# schematic.net
KiCad netlist of a schematic drawn in EAGLE
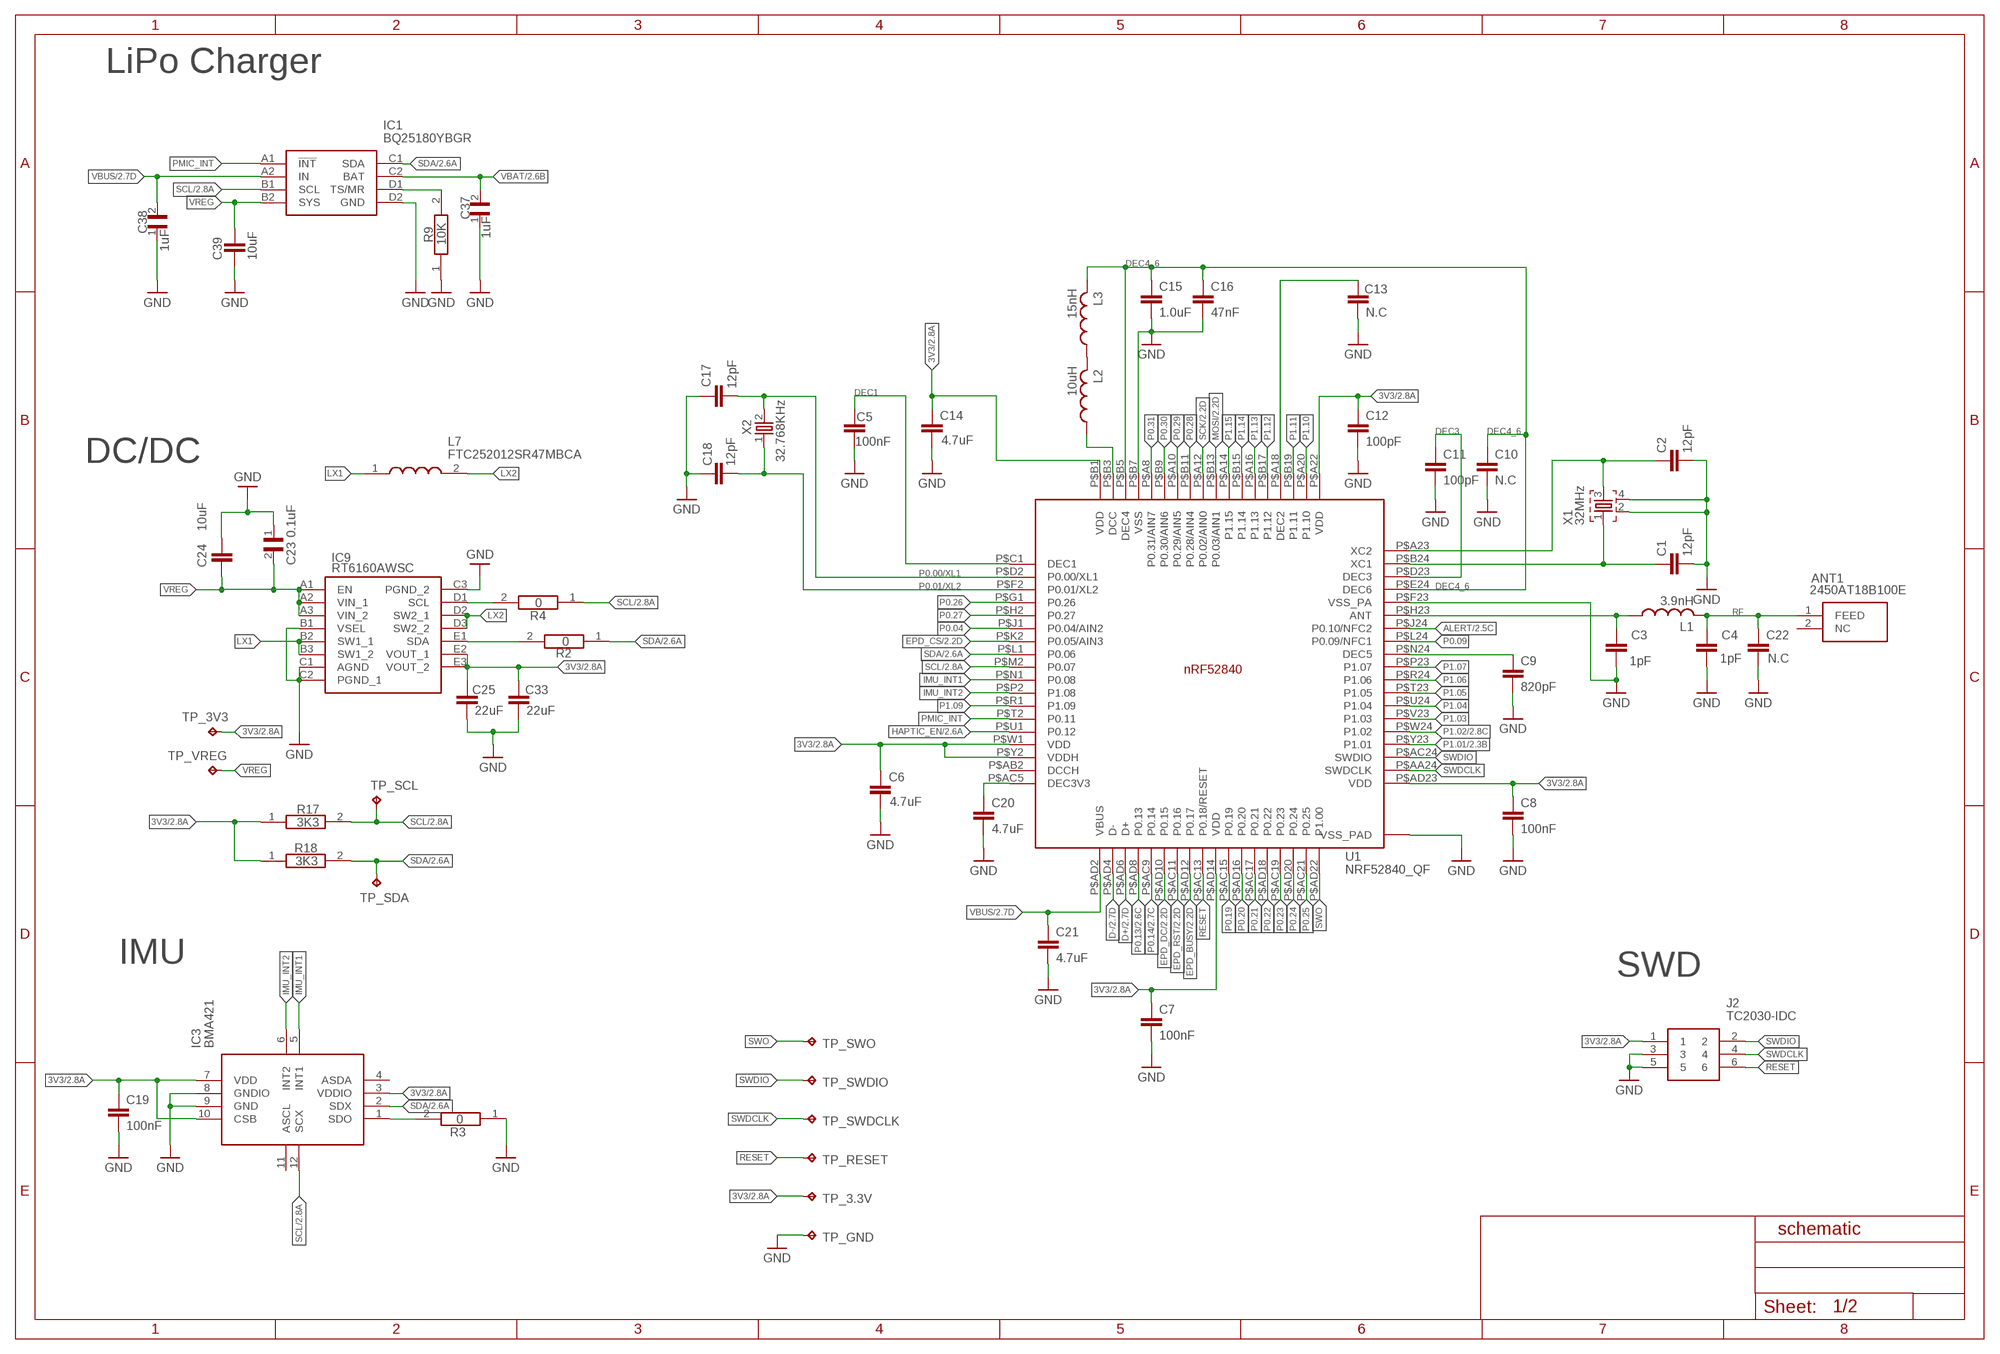
[diagram p0: schematic, sheet 1]
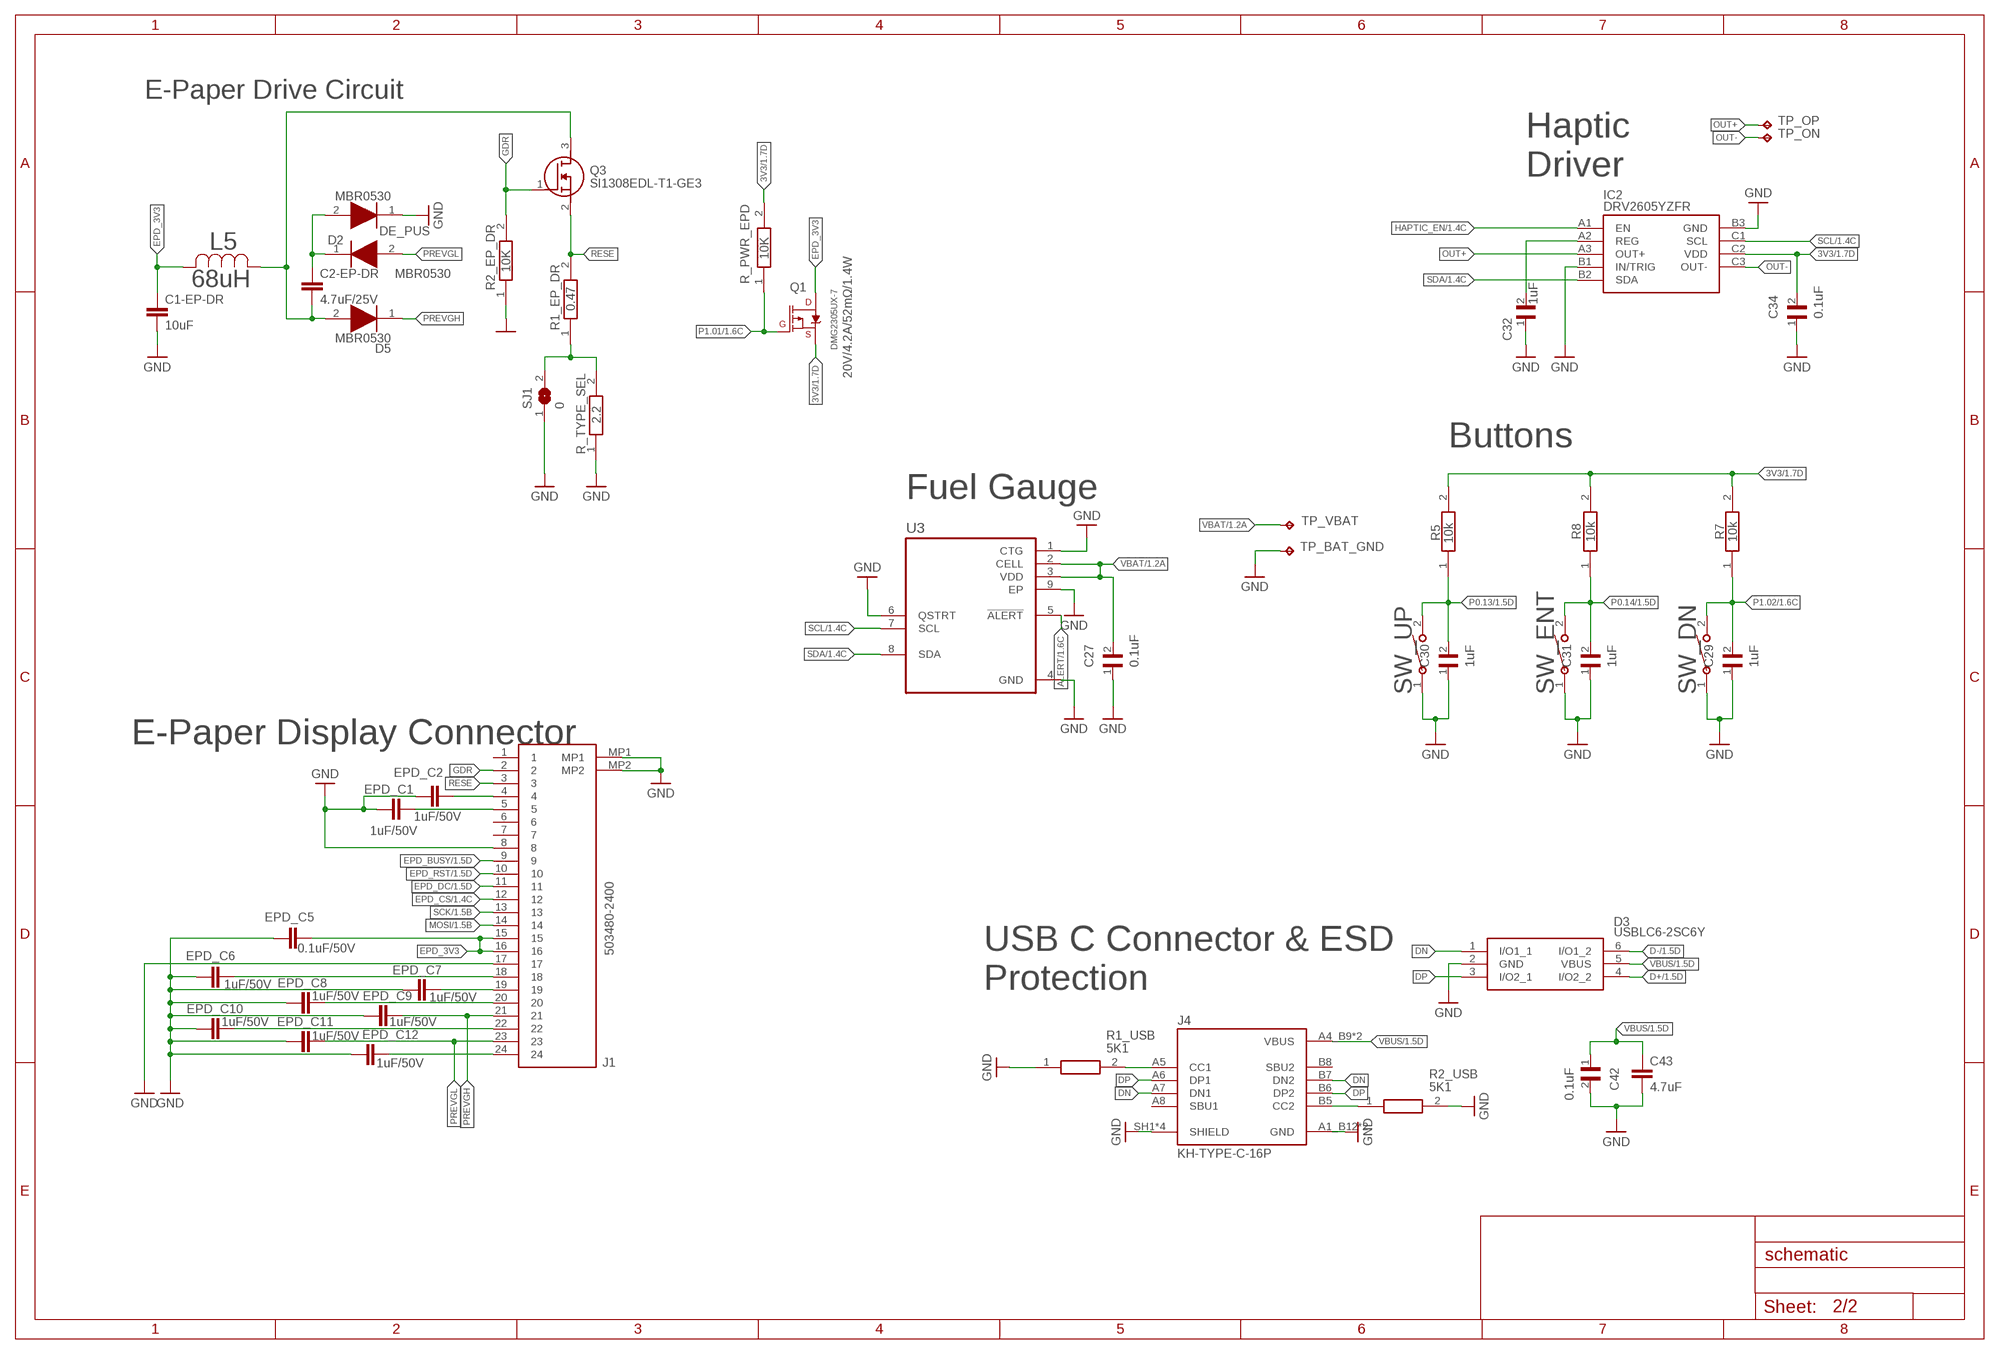
[diagram p1: schematic, sheet 2]

(export (version "E")
  (design (tool "Eeschema 10.0.6"))
  (components
    (comp (ref "ANT1")
      (value "2450AT18B100E")
      (footprint "eagle-import:2450AT18B100E_ANTC3216X140N")
      (fields (field (name "MOUSER_PART_NUMBER") "609-2450AT18B100E"))
      (libsource (lib "eagle-import") (part "2450AT18B100E_2450AT18B100E"))
    )
    (comp (ref "C1")
      (value "12pF")
      (footprint "eagle-import:NORDIC_NRF_3_RESC0201_L")
      (libsource (lib "eagle-import") (part "NORDIC_NRF_3_CAPACITOR_0201_L"))
    )
    (comp (ref "C2")
      (value "12pF")
      (footprint "eagle-import:NORDIC_NRF_3_RESC0201_L")
      (libsource (lib "eagle-import") (part "NORDIC_NRF_3_CAPACITOR_0201_L"))
    )
    (comp (ref "C3")
      (value "1pF")
      (footprint "eagle-import:NORDIC_NRF_3_RESC0201_L")
      (libsource (lib "eagle-import") (part "NORDIC_NRF_3_CAPACITOR_0201_L"))
    )
    (comp (ref "C4")
      (value "1pF")
      (footprint "eagle-import:NORDIC_NRF_3_RESC0201_L")
      (libsource (lib "eagle-import") (part "NORDIC_NRF_3_CAPACITOR_0201_L"))
    )
    (comp (ref "C5")
      (value "100nF")
      (footprint "eagle-import:NORDIC_NRF_3_RESC0201_L")
      (libsource (lib "eagle-import") (part "NORDIC_NRF_3_CAPACITOR_0201_L"))
    )
    (comp (ref "C6")
      (value "4.7uF")
      (footprint "eagle-import:NORDIC_NRF_3_RESC0402_L")
      (libsource (lib "eagle-import") (part "NORDIC_NRF_3_CAPACITOR_0402_L"))
    )
    (comp (ref "C7")
      (value "100nF")
      (footprint "eagle-import:NORDIC_NRF_3_RESC0201_L")
      (libsource (lib "eagle-import") (part "NORDIC_NRF_3_CAPACITOR_0201_L"))
    )
    (comp (ref "C8")
      (value "100nF")
      (footprint "eagle-import:NORDIC_NRF_3_RESC0201_L")
      (libsource (lib "eagle-import") (part "NORDIC_NRF_3_CAPACITOR_0201_L"))
    )
    (comp (ref "C9")
      (value "820pF")
      (footprint "eagle-import:NORDIC_NRF_3_RESC0201_L")
      (libsource (lib "eagle-import") (part "NORDIC_NRF_3_CAPACITOR_0201_L"))
    )
    (comp (ref "C10")
      (value "N.C")
      (footprint "eagle-import:NORDIC_NRF_3_RESC0201_L")
      (libsource (lib "eagle-import") (part "NORDIC_NRF_3_CAPACITOR_0201_L"))
    )
    (comp (ref "C11")
      (value "100pF")
      (footprint "eagle-import:NORDIC_NRF_3_RESC0201_L")
      (libsource (lib "eagle-import") (part "NORDIC_NRF_3_CAPACITOR_0201_L"))
    )
    (comp (ref "C12")
      (value "100pF")
      (footprint "eagle-import:NORDIC_NRF_3_RESC0201_L")
      (libsource (lib "eagle-import") (part "NORDIC_NRF_3_CAPACITOR_0201_L"))
    )
    (comp (ref "C13")
      (value "N.C")
      (footprint "eagle-import:NORDIC_NRF_3_RESC0201_L")
      (libsource (lib "eagle-import") (part "NORDIC_NRF_3_CAPACITOR_0201_L"))
    )
    (comp (ref "C14")
      (value "4.7uF")
      (footprint "eagle-import:NORDIC_NRF_3_RESC0402_L")
      (libsource (lib "eagle-import") (part "NORDIC_NRF_3_CAPACITOR_0402_L"))
    )
    (comp (ref "C15")
      (value "1.0uF")
      (footprint "eagle-import:NORDIC_NRF_3_RESC0402_L")
      (libsource (lib "eagle-import") (part "NORDIC_NRF_3_CAPACITOR_0402_L"))
    )
    (comp (ref "C16")
      (value "47nF")
      (footprint "eagle-import:NORDIC_NRF_3_RESC0201_L")
      (libsource (lib "eagle-import") (part "NORDIC_NRF_3_CAPACITOR_0201_L"))
    )
    (comp (ref "C17")
      (value "12pF")
      (footprint "eagle-import:NORDIC_NRF_3_RESC0201_L")
      (libsource (lib "eagle-import") (part "NORDIC_NRF_3_CAPACITOR_0201_L"))
    )
    (comp (ref "C18")
      (value "12pF")
      (footprint "eagle-import:NORDIC_NRF_3_RESC0201_L")
      (libsource (lib "eagle-import") (part "NORDIC_NRF_3_CAPACITOR_0201_L"))
    )
    (comp (ref "C19")
      (value "100nF")
      (footprint "eagle-import:NORDIC_NRF_3_RESC0201_L")
      (libsource (lib "eagle-import") (part "NORDIC_NRF_3_CAPACITOR_0201_L"))
    )
    (comp (ref "C20")
      (value "4.7uF")
      (footprint "eagle-import:NORDIC_NRF_3_RESC0402_L")
      (libsource (lib "eagle-import") (part "NORDIC_NRF_3_CAPACITOR_0402_L"))
    )
    (comp (ref "C21")
      (value "4.7uF")
      (footprint "eagle-import:NORDIC_NRF_3_RESC0402_L")
      (libsource (lib "eagle-import") (part "NORDIC_NRF_3_CAPACITOR_0402_L"))
    )
    (comp (ref "C22")
      (value "N.C")
      (footprint "eagle-import:NORDIC_NRF_3_RESC0201_L")
      (libsource (lib "eagle-import") (part "NORDIC_NRF_3_CAPACITOR_0201_L"))
    )
    (comp (ref "C23")
      (value "0.1uF")
      (footprint "eagle-import:GRM011R60J152KE01L_2_CAPC0201X13N")
      (fields (field (name "MF") "Murata") (field (name "MP") "GRM011R60J152KE01L"))
      (libsource (lib "eagle-import") (part "GRM011R60J152KE01L_2_GRM011R60J152KE01L"))
    )
    (comp (ref "C24")
      (value "10uF")
      (footprint "eagle-import:NORDIC_NRF_3_RESC0402_L")
      (libsource (lib "eagle-import") (part "NORDIC_NRF_3_CAPACITOR_0402_L"))
    )
    (comp (ref "C25")
      (value "22uF")
      (footprint "eagle-import:NORDIC_NRF_3_RESC0402_L")
      (libsource (lib "eagle-import") (part "NORDIC_NRF_3_CAPACITOR_0402_L"))
    )
    (comp (ref "C33")
      (value "22uF")
      (footprint "eagle-import:NORDIC_NRF_3_RESC0402_L")
      (libsource (lib "eagle-import") (part "NORDIC_NRF_3_CAPACITOR_0402_L"))
    )
    (comp (ref "C37")
      (value "1uF")
      (footprint "eagle-import:GRM011R60J152KE01L_2_CAPC0201X13N")
      (fields (field (name "MF") "Murata") (field (name "MP") "GRM011R60J152KE01L"))
      (libsource (lib "eagle-import") (part "GRM011R60J152KE01L_2_GRM011R60J152KE01L"))
    )
    (comp (ref "C38")
      (value "1uF")
      (footprint "eagle-import:GRM011R60J152KE01L_2_CAPC0201X13N")
      (fields (field (name "MF") "Murata") (field (name "MP") "GRM011R60J152KE01L"))
      (libsource (lib "eagle-import") (part "GRM011R60J152KE01L_2_GRM011R60J152KE01L"))
    )
    (comp (ref "C39")
      (value "10uF")
      (footprint "eagle-import:NORDIC_NRF_3_RESC0402_L")
      (libsource (lib "eagle-import") (part "NORDIC_NRF_3_CAPACITOR_0402_L"))
    )
    (comp (ref "IC1")
      (value "BQ25180YBGR")
      (footprint "eagle-import:BQ25180YBGR_BGA8C40P2X4_100X155X50")
      (fields (field (name "MOUSER_PART_NUMBER") "595-BQ25180YBGR"))
      (libsource (lib "eagle-import") (part "BQ25180YBGR_BQ25180YBGR"))
    )
    (comp (ref "IC3")
      (value "BMA421")
      (footprint "eagle-import:BMA423_BMA423")
      (fields (field (name "ARROW_PART_NUMBER") "BMA423") (field (name "MOUSER_PART_NUMBER") "262-BMA423"))
      (libsource (lib "eagle-import") (part "BMA423_BMA423"))
    )
    (comp (ref "IC9")
      (value "RT6160AWSC")
      (footprint "eagle-import:RT6160AWSC_BGA15C40P3X5_140X230X60")
      (fields (field (name "MOUSER_PART_NUMBER") "835-RT6160AWSC"))
      (libsource (lib "eagle-import") (part "RT6160AWSC_RT6160AWSC"))
    )
    (comp (ref "J2")
      (value "TC2030-IDC")
      (footprint "eagle-import:TC2030-IDC_TC2030IDC")
      (libsource (lib "eagle-import") (part "TC2030-IDC_TC2030-IDC"))
    )
    (comp (ref "L1")
      (value "3.9nH")
      (footprint "eagle-import:NORDIC_NRF_2_RESC0402_L")
      (libsource (lib "eagle-import") (part "NORDIC_NRF_2_INDUCTOR_0402_L"))
    )
    (comp (ref "L2")
      (value "10uH")
      (footprint "eagle-import:NORDIC_NRF_2_RESC0603_L")
      (libsource (lib "eagle-import") (part "NORDIC_NRF_2_INDUCTOR_0603_L"))
    )
    (comp (ref "L3")
      (value "15nH")
      (footprint "eagle-import:NORDIC_NRF_2_RESC0201_L")
      (libsource (lib "eagle-import") (part "NORDIC_NRF_2_INDUCTOR_0201_L"))
    )
    (comp (ref "L7")
      (value "FTC252012SR47MBCA")
      (footprint "eagle-import:MLP2016SR47MT0S1_INDC2016X100N")
      (libsource (lib "eagle-import") (part "MLP2016SR47MT0S1_FTC252012SR47MBCA"))
    )
    (comp (ref "R2")
      (value "0")
      (footprint "eagle-import:CPF0201D7K68C1_0201")
      (libsource (lib "eagle-import") (part "CPF0201D7K68C1_CPF0201D7K68C1"))
    )
    (comp (ref "R3")
      (value "0")
      (footprint "eagle-import:CPF0201D7K68C1_0201")
      (libsource (lib "eagle-import") (part "CPF0201D7K68C1_CPF0201D7K68C1"))
    )
    (comp (ref "R4")
      (value "0")
      (footprint "eagle-import:CPF0201D7K68C1_0201")
      (libsource (lib "eagle-import") (part "CPF0201D7K68C1_CPF0201D7K68C1"))
    )
    (comp (ref "R9")
      (value "10K")
      (footprint "eagle-import:CPF0201D7K68C1_0201")
      (libsource (lib "eagle-import") (part "CPF0201D7K68C1_CPF0201D7K68C1"))
    )
    (comp (ref "R17")
      (value "3K3")
      (footprint "eagle-import:CPF0201D7K68C1_0201")
      (libsource (lib "eagle-import") (part "CPF0201D7K68C1_CPF0201D7K68C1"))
    )
    (comp (ref "R18")
      (value "3K3")
      (footprint "eagle-import:CPF0201D7K68C1_0201")
      (libsource (lib "eagle-import") (part "CPF0201D7K68C1_CPF0201D7K68C1"))
    )
    (comp (ref "TP_3.3V")
      (value "HECTOR_WATCH_1_TPTP20R")
      (footprint "eagle-import:HECTOR_WATCH_1_TP20R")
      (libsource (lib "eagle-import") (part "HECTOR_WATCH_1_TPTP20R"))
    )
    (comp (ref "TP_3V3")
      (value "HECTOR_WATCH_1_TPTP20R")
      (footprint "eagle-import:HECTOR_WATCH_1_TP20R")
      (libsource (lib "eagle-import") (part "HECTOR_WATCH_1_TPTP20R"))
    )
    (comp (ref "TP_GND")
      (value "HECTOR_WATCH_1_TPTP20R")
      (footprint "eagle-import:HECTOR_WATCH_1_TP20R")
      (libsource (lib "eagle-import") (part "HECTOR_WATCH_1_TPTP20R"))
    )
    (comp (ref "TP_RESET")
      (value "HECTOR_WATCH_1_TPTP20R")
      (footprint "eagle-import:HECTOR_WATCH_1_TP20R")
      (libsource (lib "eagle-import") (part "HECTOR_WATCH_1_TPTP20R"))
    )
    (comp (ref "TP_SCL")
      (value "HECTOR_WATCH_1_TPTP20R")
      (footprint "eagle-import:HECTOR_WATCH_1_TP20R")
      (libsource (lib "eagle-import") (part "HECTOR_WATCH_1_TPTP20R"))
    )
    (comp (ref "TP_SDA")
      (value "HECTOR_WATCH_1_TPTP20R")
      (footprint "eagle-import:HECTOR_WATCH_1_TP20R")
      (libsource (lib "eagle-import") (part "HECTOR_WATCH_1_TPTP20R"))
    )
    (comp (ref "TP_SWDCLK")
      (value "HECTOR_WATCH_1_TPTP20R")
      (footprint "eagle-import:HECTOR_WATCH_1_TP20R")
      (libsource (lib "eagle-import") (part "HECTOR_WATCH_1_TPTP20R"))
    )
    (comp (ref "TP_SWDIO")
      (value "HECTOR_WATCH_1_TPTP20R")
      (footprint "eagle-import:HECTOR_WATCH_1_TP20R")
      (libsource (lib "eagle-import") (part "HECTOR_WATCH_1_TPTP20R"))
    )
    (comp (ref "TP_SWO")
      (value "HECTOR_WATCH_1_TPTP20R")
      (footprint "eagle-import:HECTOR_WATCH_1_TP20R")
      (libsource (lib "eagle-import") (part "HECTOR_WATCH_1_TPTP20R"))
    )
    (comp (ref "TP_VREG")
      (value "HECTOR_WATCH_1_TPTP20R")
      (footprint "eagle-import:HECTOR_WATCH_1_TP20R")
      (libsource (lib "eagle-import") (part "HECTOR_WATCH_1_TPTP20R"))
    )
    (comp (ref "U1")
      (value "NRF52840_QF")
      (footprint "eagle-import:NORDIC_NRF_4_AQFN50P700X700X85_HS-74N")
      (libsource (lib "eagle-import") (part "NORDIC_NRF_4_NRF52840_QF"))
    )
    (comp (ref "X1")
      (value "32MHz")
      (footprint "eagle-import:NORDIC_NRF_BT-XTAL_2016_N")
      (libsource (lib "eagle-import") (part "NORDIC_NRF_XTAL_32MHZ"))
    )
    (comp (ref "X2")
      (value "32.768KHz")
      (footprint "eagle-import:NORDIC_NRF_1_XTAL_3215_N")
      (libsource (lib "eagle-import") (part "NORDIC_NRF_1_XTAL_32KHZ"))
    )
    (comp (ref "C1-EP-DR")
      (value "10uF")
      (footprint "eagle-import:NORDIC_NRF_3_RESC0402_L")
      (libsource (lib "eagle-import") (part "NORDIC_NRF_3_CAPACITOR_0402_L"))
    )
    (comp (ref "C2-EP-DR")
      (value "4.7uF/25V")
      (footprint "eagle-import:NORDIC_NRF_3_RESC0402_L")
      (libsource (lib "eagle-import") (part "NORDIC_NRF_3_CAPACITOR_0402_L"))
    )
    (comp (ref "C27")
      (value "0.1uF")
      (footprint "eagle-import:GRM011R60J152KE01L_2_CAPC0201X13N")
      (fields (field (name "MF") "Murata") (field (name "MP") "GRM011R60J152KE01L"))
      (libsource (lib "eagle-import") (part "GRM011R60J152KE01L_2_GRM011R60J152KE01L"))
    )
    (comp (ref "C29")
      (value "1uF")
      (footprint "eagle-import:GRM011R60J152KE01L_2_CAPC0201X13N")
      (fields (field (name "MF") "Murata") (field (name "MP") "GRM011R60J152KE01L"))
      (libsource (lib "eagle-import") (part "GRM011R60J152KE01L_2_GRM011R60J152KE01L"))
    )
    (comp (ref "C30")
      (value "1uF")
      (footprint "eagle-import:GRM011R60J152KE01L_2_CAPC0201X13N")
      (fields (field (name "MF") "Murata") (field (name "MP") "GRM011R60J152KE01L"))
      (libsource (lib "eagle-import") (part "GRM011R60J152KE01L_2_GRM011R60J152KE01L"))
    )
    (comp (ref "C31")
      (value "1uF")
      (footprint "eagle-import:GRM011R60J152KE01L_2_CAPC0201X13N")
      (fields (field (name "MF") "Murata") (field (name "MP") "GRM011R60J152KE01L"))
      (libsource (lib "eagle-import") (part "GRM011R60J152KE01L_2_GRM011R60J152KE01L"))
    )
    (comp (ref "C32")
      (value "1uF")
      (footprint "eagle-import:GRM011R60J152KE01L_2_CAPC0201X13N")
      (fields (field (name "MF") "Murata") (field (name "MP") "GRM011R60J152KE01L"))
      (libsource (lib "eagle-import") (part "GRM011R60J152KE01L_2_GRM011R60J152KE01L"))
    )
    (comp (ref "C34")
      (value "0.1uF")
      (footprint "eagle-import:GRM011R60J152KE01L_2_CAPC0201X13N")
      (fields (field (name "MF") "Murata") (field (name "MP") "GRM011R60J152KE01L"))
      (libsource (lib "eagle-import") (part "GRM011R60J152KE01L_2_GRM011R60J152KE01L"))
    )
    (comp (ref "C42")
      (value "0.1uF")
      (footprint "eagle-import:GRM011R60J152KE01L_2_CAPC0201X13N")
      (fields (field (name "MF") "Murata") (field (name "MP") "GRM011R60J152KE01L"))
      (libsource (lib "eagle-import") (part "GRM011R60J152KE01L_2_GRM011R60J152KE01L"))
    )
    (comp (ref "C43")
      (value "4.7uF")
      (footprint "eagle-import:NORDIC_NRF_3_RESC0402_L")
      (libsource (lib "eagle-import") (part "NORDIC_NRF_3_CAPACITOR_0402_L"))
    )
    (comp (ref "D2")
      (value "MBR0530")
      (footprint "eagle-import:ESP32_C6_LIBRARY_5_SOD3716X135N")
      (fields (field (name "MF") "ON Semiconductor"))
      (libsource (lib "eagle-import") (part "ESP32_C6_LIBRARY_5_MBR0530"))
    )
    (comp (ref "D3")
      (value "USBLC6-2SC6Y")
      (footprint "eagle-import:ESP32_C6_LIBRARY_3_SOT95P280X145-6N")
      (fields (field (name "MF") "STMicroelectronics"))
      (libsource (lib "eagle-import") (part "ESP32_C6_LIBRARY_3_USBLC6-2SC6Y"))
    )
    (comp (ref "D5")
      (value "MBR0530")
      (footprint "eagle-import:ESP32_C6_LIBRARY_5_SOD3716X135N")
      (fields (field (name "MF") "ON Semiconductor"))
      (libsource (lib "eagle-import") (part "ESP32_C6_LIBRARY_5_MBR0530"))
    )
    (comp (ref "DE_PUS")
      (value "MBR0530")
      (footprint "eagle-import:ESP32_C6_LIBRARY_5_SOD3716X135N")
      (fields (field (name "MF") "ON Semiconductor"))
      (libsource (lib "eagle-import") (part "ESP32_C6_LIBRARY_5_MBR0530"))
    )
    (comp (ref "EPD_C1")
      (value "1uF/50V")
      (footprint "eagle-import:NORDIC_NRF_3_RESC0402_L")
      (libsource (lib "eagle-import") (part "NORDIC_NRF_3_CAPACITOR_0402_L"))
    )
    (comp (ref "EPD_C2")
      (value "1uF/50V")
      (footprint "eagle-import:NORDIC_NRF_3_RESC0402_L")
      (libsource (lib "eagle-import") (part "NORDIC_NRF_3_CAPACITOR_0402_L"))
    )
    (comp (ref "EPD_C5")
      (value "0.1uF/50V")
      (footprint "eagle-import:NORDIC_NRF_3_RESC0402_L")
      (libsource (lib "eagle-import") (part "NORDIC_NRF_3_CAPACITOR_0402_L"))
    )
    (comp (ref "EPD_C6")
      (value "1uF/50V")
      (footprint "eagle-import:NORDIC_NRF_3_RESC0402_L")
      (libsource (lib "eagle-import") (part "NORDIC_NRF_3_CAPACITOR_0402_L"))
    )
    (comp (ref "EPD_C7")
      (value "1uF/50V")
      (footprint "eagle-import:NORDIC_NRF_3_RESC0402_L")
      (libsource (lib "eagle-import") (part "NORDIC_NRF_3_CAPACITOR_0402_L"))
    )
    (comp (ref "EPD_C8")
      (value "1uF/50V")
      (footprint "eagle-import:NORDIC_NRF_3_RESC0402_L")
      (libsource (lib "eagle-import") (part "NORDIC_NRF_3_CAPACITOR_0402_L"))
    )
    (comp (ref "EPD_C9")
      (value "1uF/50V")
      (footprint "eagle-import:NORDIC_NRF_3_RESC0402_L")
      (libsource (lib "eagle-import") (part "NORDIC_NRF_3_CAPACITOR_0402_L"))
    )
    (comp (ref "EPD_C10")
      (value "1uF/50V")
      (footprint "eagle-import:NORDIC_NRF_3_RESC0402_L")
      (libsource (lib "eagle-import") (part "NORDIC_NRF_3_CAPACITOR_0402_L"))
    )
    (comp (ref "EPD_C11")
      (value "1uF/50V")
      (footprint "eagle-import:NORDIC_NRF_3_RESC0402_L")
      (libsource (lib "eagle-import") (part "NORDIC_NRF_3_CAPACITOR_0402_L"))
    )
    (comp (ref "EPD_C12")
      (value "1uF/50V")
      (footprint "eagle-import:NORDIC_NRF_3_RESC0402_L")
      (libsource (lib "eagle-import") (part "NORDIC_NRF_3_CAPACITOR_0402_L"))
    )
    (comp (ref "IC2")
      (value "DRV2605YZFR")
      (footprint "eagle-import:DRV2605YZFR_BGA9C50P3X3_144X144X62")
      (libsource (lib "eagle-import") (part "DRV2605YZFR_DRV2605YZFR"))
    )
    (comp (ref "J1")
      (value "503480-2400")
      (footprint "eagle-import:503480-2400_5034802400")
      (fields (field (name "MOUSER_PART_NUMBER") "538-503480-2400"))
      (libsource (lib "eagle-import") (part "503480-2400_503480-2400"))
    )
    (comp (ref "J4")
      (value "KH-TYPE-C-16P")
      (footprint "eagle-import:KH-TYPE-C-16P_KINGHELM_KH-TYPE-C-16P")
      (fields (field (name "MF") "kinghelm"))
      (libsource (lib "eagle-import") (part "KH-TYPE-C-16P_KH-TYPE-C-16P"))
    )
    (comp (ref "L5")
      (value "68uH")
      (footprint "eagle-import:ESP32_C6_LIBRARY_2_IND_4828-WE-TPC_WRE")
      (fields
        (field (name "MANUFACTURER_PART_NUMBER") "744043680")
        (field (name "COPYRIGHT") "Copyright (C) 2024 Ultra Librarian. All rights reserved.")
      )
      (libsource (lib "eagle-import") (part "ESP32_C6_LIBRARY_2_744043680IND_4828-WE-TPC_WRE"))
    )
    (comp (ref "Q1")
      (value "20V/4.2A/52mΩ/1.4W")
      (footprint "eagle-import:ESP32_C6_LIBRARY_4_ESP32_C6_LIBRARY_4_ESP32_C6_LIBRARY_4_ESP32_C6_LIBRARY_4_ESP32_WROVER_SPARKFUN-DISCRETESEMI_SOT23-3")
      (libsource (lib "eagle-import") (part "ESP32_C6_LIBRARY_4_ESP32_WROVER_SPARKFUN-DISCRETESEMI_MOSFET_PCH-DMG2305UX-7"))
    )
    (comp (ref "Q3")
      (value "SI1308EDL-T1-GE3")
      (footprint "eagle-import:ESP32_C6_LIBRARY_6_SOT65P210X110-3N")
      (fields (field (name "MF") "Vishay Siliconix"))
      (libsource (lib "eagle-import") (part "ESP32_C6_LIBRARY_6_SI1308EDL-T1-GE3"))
    )
    (comp (ref "R1_EP_DR")
      (value "0.47")
      (footprint "eagle-import:CPF0201D7K68C1_0201")
      (libsource (lib "eagle-import") (part "CPF0201D7K68C1_CPF0201D7K68C1"))
    )
    (comp (ref "R1_USB")
      (value "5K1")
      (footprint "eagle-import:CPF0201D7K68C1_0201")
      (libsource (lib "eagle-import") (part "CPF0201D7K68C1_CPF0201D7K68C1"))
    )
    (comp (ref "R2_EP_DR")
      (value "10K")
      (footprint "eagle-import:CPF0201D7K68C1_0201")
      (libsource (lib "eagle-import") (part "CPF0201D7K68C1_CPF0201D7K68C1"))
    )
    (comp (ref "R2_USB")
      (value "5K1")
      (footprint "eagle-import:CPF0201D7K68C1_0201")
      (libsource (lib "eagle-import") (part "CPF0201D7K68C1_CPF0201D7K68C1"))
    )
    (comp (ref "R5")
      (value "10k")
      (footprint "eagle-import:CPF0201D7K68C1_0201")
      (libsource (lib "eagle-import") (part "CPF0201D7K68C1_CPF0201D7K68C1"))
    )
    (comp (ref "R7")
      (value "10k")
      (footprint "eagle-import:CPF0201D7K68C1_0201")
      (libsource (lib "eagle-import") (part "CPF0201D7K68C1_CPF0201D7K68C1"))
    )
    (comp (ref "R8")
      (value "10k")
      (footprint "eagle-import:CPF0201D7K68C1_0201")
      (libsource (lib "eagle-import") (part "CPF0201D7K68C1_CPF0201D7K68C1"))
    )
    (comp (ref "R_PWR_EPD")
      (value "10K")
      (footprint "eagle-import:CPF0201D7K68C1_0201")
      (libsource (lib "eagle-import") (part "CPF0201D7K68C1_CPF0201D7K68C1"))
    )
    (comp (ref "R_TYPE_SEL")
      (value "2.2")
      (footprint "eagle-import:CPF0201D7K68C1_0201")
      (libsource (lib "eagle-import") (part "CPF0201D7K68C1_CPF0201D7K68C1"))
    )
    (comp (ref "SJ1")
      (value "0")
      (footprint "eagle-import:ESP32_C6_LIBRARY_7_JUMPER_SJ")
      (libsource (lib "eagle-import") (part "ESP32_C6_LIBRARY_7_JUMPER_SJ"))
    )
    (comp (ref "SW_DN")
      (value "2025-10-22_07-23-44_LIBRARY_EVP-AKE31ASW_EVP-AKE31A_PAN")
      (footprint "eagle-import:2025-10-22_07-23-44_LIBRARY_SW_EVP-AKE31A_PAN")
      (fields
        (field (name "MANUFACTURER_PART_NUMBER") "EVP-AKE31A")
        (field (name "COPYRIGHT") "Copyright (C) 2025 Ultra Librarian. All rights reserved.")
      )
      (libsource (lib "eagle-import") (part "2025-10-22_07-23-44_LIBRARY_EVP-AKE31ASW_EVP-AKE31A_PAN"))
    )
    (comp (ref "SW_ENT")
      (value "2025-10-22_07-23-44_LIBRARY_EVP-AKE31ASW_EVP-AKE31A_PAN")
      (footprint "eagle-import:2025-10-22_07-23-44_LIBRARY_SW_EVP-AKE31A_PAN")
      (fields
        (field (name "MANUFACTURER_PART_NUMBER") "EVP-AKE31A")
        (field (name "COPYRIGHT") "Copyright (C) 2025 Ultra Librarian. All rights reserved.")
      )
      (libsource (lib "eagle-import") (part "2025-10-22_07-23-44_LIBRARY_EVP-AKE31ASW_EVP-AKE31A_PAN"))
    )
    (comp (ref "SW_UP")
      (value "2025-10-22_07-23-44_LIBRARY_EVP-AKE31ASW_EVP-AKE31A_PAN")
      (footprint "eagle-import:2025-10-22_07-23-44_LIBRARY_SW_EVP-AKE31A_PAN")
      (fields
        (field (name "MANUFACTURER_PART_NUMBER") "EVP-AKE31A")
        (field (name "COPYRIGHT") "Copyright (C) 2025 Ultra Librarian. All rights reserved.")
      )
      (libsource (lib "eagle-import") (part "2025-10-22_07-23-44_LIBRARY_EVP-AKE31ASW_EVP-AKE31A_PAN"))
    )
    (comp (ref "TP_BAT_GND")
      (value "HECTOR_WATCH_1_TPTP20R")
      (footprint "eagle-import:HECTOR_WATCH_1_TP20R")
      (libsource (lib "eagle-import") (part "HECTOR_WATCH_1_TPTP20R"))
    )
    (comp (ref "TP_ON")
      (value "HECTOR_WATCH_1_TPTP20R")
      (footprint "eagle-import:HECTOR_WATCH_1_TP20R")
      (libsource (lib "eagle-import") (part "HECTOR_WATCH_1_TPTP20R"))
    )
    (comp (ref "TP_OP")
      (value "HECTOR_WATCH_1_TPTP20R")
      (footprint "eagle-import:HECTOR_WATCH_1_TP20R")
      (libsource (lib "eagle-import") (part "HECTOR_WATCH_1_TPTP20R"))
    )
    (comp (ref "TP_VBAT")
      (value "HECTOR_WATCH_1_TPTP20R")
      (footprint "eagle-import:HECTOR_WATCH_1_TP20R")
      (libsource (lib "eagle-import") (part "HECTOR_WATCH_1_TPTP20R"))
    )
    (comp (ref "U3")
      (value "ESP32_C6_LIBRARY_MAX17048G+T10")
      (footprint "eagle-import:ESP32_C6_LIBRARY_SON50P200X200X80-9N")
      (fields (field (name "MF") "Analog Devices") (field (name "MP") "MAX17048G+T10"))
      (libsource (lib "eagle-import") (part "ESP32_C6_LIBRARY_MAX17048G+T10"))
    )
  )
  (nets
    (net (code "1") (name "3V3") (class "Default")
      (node (ref "C12") (pin "1") (pinfunction "1_1") (pintype "passive"))
      (node (ref "C14") (pin "2") (pinfunction "2_2") (pintype "passive"))
      (node (ref "C19") (pin "1") (pinfunction "1_1") (pintype "passive"))
      (node (ref "C25") (pin "1") (pinfunction "1_1") (pintype "passive"))
      (node (ref "C33") (pin "1") (pinfunction "1_1") (pintype "passive"))
      (node (ref "C34") (pin "2") (pinfunction "2_2") (pintype "passive"))
      (node (ref "C6") (pin "2") (pinfunction "2_2") (pintype "passive"))
      (node (ref "C7") (pin "1") (pinfunction "1_1") (pintype "passive"))
      (node (ref "C8") (pin "1") (pinfunction "1_1") (pintype "passive"))
      (node (ref "IC2") (pin "C2") (pinfunction "VDD_C2") (pintype "bidirectional"))
      (node (ref "IC3") (pin "10") (pinfunction "CSB_10") (pintype "bidirectional"))
      (node (ref "IC3") (pin "3") (pinfunction "VDDIO_3") (pintype "bidirectional"))
      (node (ref "IC3") (pin "7") (pinfunction "VDD_7") (pintype "bidirectional"))
      (node (ref "IC9") (pin "E2") (pinfunction "VOUT_1_E2") (pintype "bidirectional"))
      (node (ref "IC9") (pin "E3") (pinfunction "VOUT_2_E3") (pintype "bidirectional"))
      (node (ref "J2") (pin "1") (pinfunction "1_1") (pintype "bidirectional"))
      (node (ref "Q1") (pin "2") (pinfunction "S_2") (pintype "bidirectional"))
      (node (ref "R17") (pin "1") (pinfunction "1_1") (pintype "bidirectional"))
      (node (ref "R18") (pin "1") (pinfunction "1_1") (pintype "bidirectional"))
      (node (ref "R5") (pin "2") (pinfunction "2_2") (pintype "bidirectional"))
      (node (ref "R7") (pin "2") (pinfunction "2_2") (pintype "bidirectional"))
      (node (ref "R8") (pin "2") (pinfunction "2_2") (pintype "bidirectional"))
      (node (ref "R_PWR_EPD") (pin "2") (pinfunction "2_2") (pintype "bidirectional"))
      (node (ref "TP_3.3V") (pin "TP") (pinfunction "TP_TP") (pintype "input"))
      (node (ref "TP_3V3") (pin "TP") (pinfunction "TP_TP") (pintype "input"))
      (node (ref "U1") (pin "P$A22") (pinfunction "VDD_P$A22") (pintype "power_in"))
      (node (ref "U1") (pin "P$AD14") (pinfunction "VDD_P$AD14") (pintype "power_in"))
      (node (ref "U1") (pin "P$AD23") (pinfunction "VDD_P$AD23") (pintype "power_in"))
      (node (ref "U1") (pin "P$B1") (pinfunction "VDD_P$B1") (pintype "power_in"))
      (node (ref "U1") (pin "P$W1") (pinfunction "VDD_P$W1") (pintype "power_in"))
      (node (ref "U1") (pin "P$Y2") (pinfunction "VDDH_P$Y2") (pintype "power_in"))
    )
    (net (code "2") (name "ALERT") (class "Default")
      (node (ref "U1") (pin "P$J24") (pinfunction "P0.10/NFC2_P$J24") (pintype "bidirectional"))
      (node (ref "U3") (pin "5") (pinfunction "~{ALERT}_5") (pintype "output"))
    )
    (net (code "3") (name "D+") (class "Default")
      (node (ref "D3") (pin "4") (pinfunction "I/O2_2_4") (pintype "bidirectional"))
      (node (ref "U1") (pin "P$AD6") (pinfunction "D+_P$AD6") (pintype "bidirectional"))
    )
    (net (code "4") (name "D-") (class "Default")
      (node (ref "D3") (pin "6") (pinfunction "I/O1_2_6") (pintype "bidirectional"))
      (node (ref "U1") (pin "P$AD4") (pinfunction "D-_P$AD4") (pintype "bidirectional"))
    )
    (net (code "5") (name "DN") (class "Default")
      (node (ref "D3") (pin "1") (pinfunction "I/O1_1_1") (pintype "bidirectional"))
      (node (ref "J4") (pin "A7") (pinfunction "DN1_A7") (pintype "bidirectional"))
      (node (ref "J4") (pin "B7") (pinfunction "DN2_B7") (pintype "bidirectional"))
    )
    (net (code "6") (name "DP") (class "Default")
      (node (ref "D3") (pin "3") (pinfunction "I/O2_1_3") (pintype "bidirectional"))
      (node (ref "J4") (pin "A6") (pinfunction "DP1_A6") (pintype "bidirectional"))
      (node (ref "J4") (pin "B6") (pinfunction "DP2_B6") (pintype "bidirectional"))
    )
    (net (code "7") (name "EPD_3V3") (class "Default")
      (node (ref "C1-EP-DR") (pin "1") (pinfunction "1_1") (pintype "passive"))
      (node (ref "EPD_C5") (pin "2") (pinfunction "2_2") (pintype "passive"))
      (node (ref "J1") (pin "15") (pinfunction "15_15") (pintype "bidirectional"))
      (node (ref "J1") (pin "16") (pinfunction "16_16") (pintype "bidirectional"))
      (node (ref "L5") (pin "2") (pinfunction "2_2") (pintype "passive"))
      (node (ref "Q1") (pin "3") (pinfunction "D_3") (pintype "bidirectional"))
    )
    (net (code "8") (name "EPD_BUSY") (class "Default")
      (node (ref "J1") (pin "9") (pinfunction "9_9") (pintype "bidirectional"))
      (node (ref "U1") (pin "P$AD12") (pinfunction "P0.17_P$AD12") (pintype "bidirectional"))
    )
    (net (code "9") (name "EPD_CS") (class "Default")
      (node (ref "J1") (pin "12") (pinfunction "12_12") (pintype "bidirectional"))
      (node (ref "U1") (pin "P$K2") (pinfunction "P0.05/AIN3_P$K2") (pintype "bidirectional"))
    )
    (net (code "10") (name "EPD_DC") (class "Default")
      (node (ref "J1") (pin "11") (pinfunction "11_11") (pintype "bidirectional"))
      (node (ref "U1") (pin "P$AD10") (pinfunction "P0.15_P$AD10") (pintype "bidirectional"))
    )
    (net (code "11") (name "EPD_RST") (class "Default")
      (node (ref "J1") (pin "10") (pinfunction "10_10") (pintype "bidirectional"))
      (node (ref "U1") (pin "P$AC11") (pinfunction "P0.16_P$AC11") (pintype "bidirectional"))
    )
    (net (code "12") (name "GDR") (class "Default")
      (node (ref "J1") (pin "2") (pinfunction "2_2") (pintype "bidirectional"))
      (node (ref "Q3") (pin "1") (pinfunction "G_1") (pintype "bidirectional"))
      (node (ref "R2_EP_DR") (pin "2") (pinfunction "2_2") (pintype "bidirectional"))
    )
    (net (code "13") (name "GND") (class "Default")
      (node (ref "C1") (pin "2") (pinfunction "2_2") (pintype "passive"))
      (node (ref "C1-EP-DR") (pin "2") (pinfunction "2_2") (pintype "passive"))
      (node (ref "C10") (pin "2") (pinfunction "2_2") (pintype "passive"))
      (node (ref "C11") (pin "2") (pinfunction "2_2") (pintype "passive"))
      (node (ref "C12") (pin "2") (pinfunction "2_2") (pintype "passive"))
      (node (ref "C13") (pin "2") (pinfunction "2_2") (pintype "passive"))
      (node (ref "C14") (pin "1") (pinfunction "1_1") (pintype "passive"))
      (node (ref "C15") (pin "2") (pinfunction "2_2") (pintype "passive"))
      (node (ref "C16") (pin "2") (pinfunction "2_2") (pintype "passive"))
      (node (ref "C17") (pin "2") (pinfunction "2_2") (pintype "passive"))
      (node (ref "C18") (pin "2") (pinfunction "2_2") (pintype "passive"))
      (node (ref "C19") (pin "2") (pinfunction "2_2") (pintype "passive"))
      (node (ref "C2") (pin "2") (pinfunction "2_2") (pintype "passive"))
      (node (ref "C20") (pin "1") (pinfunction "1_1") (pintype "passive"))
      (node (ref "C21") (pin "2") (pinfunction "2_2") (pintype "passive"))
      (node (ref "C22") (pin "1") (pinfunction "1_1") (pintype "passive"))
      (node (ref "C23") (pin "1") (pinfunction "1_1") (pintype "passive"))
      (node (ref "C24") (pin "1") (pinfunction "1_1") (pintype "passive"))
      (node (ref "C25") (pin "2") (pinfunction "2_2") (pintype "passive"))
      (node (ref "C27") (pin "1") (pinfunction "1_1") (pintype "passive"))
      (node (ref "C29") (pin "1") (pinfunction "1_1") (pintype "passive"))
      (node (ref "C3") (pin "1") (pinfunction "1_1") (pintype "passive"))
      (node (ref "C30") (pin "1") (pinfunction "1_1") (pintype "passive"))
      (node (ref "C31") (pin "1") (pinfunction "1_1") (pintype "passive"))
      (node (ref "C32") (pin "1") (pinfunction "1_1") (pintype "passive"))
      (node (ref "C33") (pin "2") (pinfunction "2_2") (pintype "passive"))
      (node (ref "C34") (pin "1") (pinfunction "1_1") (pintype "passive"))
      (node (ref "C37") (pin "1") (pinfunction "1_1") (pintype "passive"))
      (node (ref "C38") (pin "1") (pinfunction "1_1") (pintype "passive"))
      (node (ref "C39") (pin "2") (pinfunction "2_2") (pintype "passive"))
      (node (ref "C4") (pin "1") (pinfunction "1_1") (pintype "passive"))
      (node (ref "C42") (pin "2") (pinfunction "2_2") (pintype "passive"))
      (node (ref "C43") (pin "2") (pinfunction "2_2") (pintype "passive"))
      (node (ref "C5") (pin "1") (pinfunction "1_1") (pintype "passive"))
      (node (ref "C6") (pin "1") (pinfunction "1_1") (pintype "passive"))
      (node (ref "C7") (pin "2") (pinfunction "2_2") (pintype "passive"))
      (node (ref "C8") (pin "2") (pinfunction "2_2") (pintype "passive"))
      (node (ref "C9") (pin "2") (pinfunction "2_2") (pintype "passive"))
      (node (ref "D3") (pin "2") (pinfunction "GND_2") (pintype "bidirectional"))
      (node (ref "DE_PUS") (pin "1") (pinfunction "K_1") (pintype "bidirectional"))
      (node (ref "EPD_C1") (pin "1") (pinfunction "1_1") (pintype "passive"))
      (node (ref "EPD_C10") (pin "1") (pinfunction "1_1") (pintype "passive"))
      (node (ref "EPD_C11") (pin "1") (pinfunction "1_1") (pintype "passive"))
      (node (ref "EPD_C12") (pin "1") (pinfunction "1_1") (pintype "passive"))
      (node (ref "EPD_C2") (pin "1") (pinfunction "1_1") (pintype "passive"))
      (node (ref "EPD_C5") (pin "1") (pinfunction "1_1") (pintype "passive"))
      (node (ref "EPD_C6") (pin "1") (pinfunction "1_1") (pintype "passive"))
      (node (ref "EPD_C7") (pin "1") (pinfunction "1_1") (pintype "passive"))
      (node (ref "EPD_C8") (pin "1") (pinfunction "1_1") (pintype "passive"))
      (node (ref "EPD_C9") (pin "1") (pinfunction "1_1") (pintype "passive"))
      (node (ref "IC1") (pin "D2") (pinfunction "GND_D2") (pintype "bidirectional"))
      (node (ref "IC2") (pin "B1") (pinfunction "IN/TRIG_B1") (pintype "bidirectional"))
      (node (ref "IC2") (pin "B3") (pinfunction "GND_B3") (pintype "bidirectional"))
      (node (ref "IC3") (pin "8") (pinfunction "GNDIO_8") (pintype "bidirectional"))
      (node (ref "IC3") (pin "9") (pinfunction "GND_9") (pintype "bidirectional"))
      (node (ref "IC9") (pin "B1") (pinfunction "VSEL_B1") (pintype "bidirectional"))
      (node (ref "IC9") (pin "C1") (pinfunction "AGND_C1") (pintype "bidirectional"))
      (node (ref "IC9") (pin "C2") (pinfunction "PGND_1_C2") (pintype "bidirectional"))
      (node (ref "IC9") (pin "C3") (pinfunction "PGND_2_C3") (pintype "bidirectional"))
      (node (ref "J1") (pin "17") (pinfunction "17_17") (pintype "bidirectional"))
      (node (ref "J1") (pin "8") (pinfunction "8_8") (pintype "bidirectional"))
      (node (ref "J1") (pin "MP1") (pinfunction "MP1_MP1") (pintype "bidirectional"))
      (node (ref "J1") (pin "MP2") (pinfunction "MP2_MP2") (pintype "bidirectional"))
      (node (ref "J2") (pin "3") (pinfunction "3_3") (pintype "bidirectional"))
      (node (ref "J2") (pin "5") (pinfunction "5_5") (pintype "bidirectional"))
      (node (ref "J4") (pin "A12_B1") (pinfunction "GND_A12_B1") (pintype "power_in"))
      (node (ref "J4") (pin "A1_B12") (pinfunction "GND_A1_B12") (pintype "power_in"))
      (node (ref "J4") (pin "SH1") (pinfunction "SHIELD_SH1") (pintype "passive"))
      (node (ref "J4") (pin "SH2") (pinfunction "SHIELD_SH2") (pintype "passive"))
      (node (ref "J4") (pin "SH3") (pinfunction "SHIELD_SH3") (pintype "passive"))
      (node (ref "J4") (pin "SH4") (pinfunction "SHIELD_SH4") (pintype "passive"))
      (node (ref "R1_USB") (pin "1") (pinfunction "1_1") (pintype "bidirectional"))
      (node (ref "R2_EP_DR") (pin "1") (pinfunction "1_1") (pintype "bidirectional"))
      (node (ref "R2_USB") (pin "2") (pinfunction "2_2") (pintype "bidirectional"))
      (node (ref "R3") (pin "1") (pinfunction "1_1") (pintype "bidirectional"))
      (node (ref "R9") (pin "1") (pinfunction "1_1") (pintype "bidirectional"))
      (node (ref "R_TYPE_SEL") (pin "1") (pinfunction "1_1") (pintype "bidirectional"))
      (node (ref "SJ1") (pin "1") (pinfunction "1_1") (pintype "passive"))
      (node (ref "SW_DN") (pin "1") (pinfunction "1_1") (pintype "passive"))
      (node (ref "SW_ENT") (pin "1") (pinfunction "1_1") (pintype "passive"))
      (node (ref "SW_UP") (pin "1") (pinfunction "1_1") (pintype "passive"))
      (node (ref "TP_BAT_GND") (pin "TP") (pinfunction "TP_TP") (pintype "input"))
      (node (ref "TP_GND") (pin "TP") (pinfunction "TP_TP") (pintype "input"))
      (node (ref "U1") (pin "P$74") (pinfunction "VSS_PAD_P$74") (pintype "bidirectional"))
      (node (ref "U1") (pin "P$75") (pinfunction "VSS_PAD_P$75") (pintype "bidirectional"))
      (node (ref "U1") (pin "P$76") (pinfunction "VSS_PAD_P$76") (pintype "bidirectional"))
      (node (ref "U1") (pin "P$77") (pinfunction "VSS_PAD_P$77") (pintype "bidirectional"))
      (node (ref "U1") (pin "P$78") (pinfunction "VSS_PAD_P$78") (pintype "bidirectional"))
      (node (ref "U1") (pin "P$79") (pinfunction "VSS_PAD_P$79") (pintype "bidirectional"))
      (node (ref "U1") (pin "P$80") (pinfunction "VSS_PAD_P$80") (pintype "bidirectional"))
      (node (ref "U1") (pin "P$81") (pinfunction "VSS_PAD_P$81") (pintype "bidirectional"))
      (node (ref "U1") (pin "P$82") (pinfunction "VSS_PAD_P$82") (pintype "bidirectional"))
      (node (ref "U1") (pin "P$83") (pinfunction "VSS_PAD_P$83") (pintype "bidirectional"))
      (node (ref "U1") (pin "P$84") (pinfunction "VSS_PAD_P$84") (pintype "bidirectional"))
      (node (ref "U1") (pin "P$85") (pinfunction "VSS_PAD_P$85") (pintype "bidirectional"))
      (node (ref "U1") (pin "P$86") (pinfunction "VSS_PAD_P$86") (pintype "bidirectional"))
      (node (ref "U1") (pin "P$87") (pinfunction "VSS_PAD_P$87") (pintype "bidirectional"))
      (node (ref "U1") (pin "P$88") (pinfunction "VSS_PAD_P$88") (pintype "bidirectional"))
      (node (ref "U1") (pin "P$89") (pinfunction "VSS_PAD_P$89") (pintype "bidirectional"))
      (node (ref "U1") (pin "P$90") (pinfunction "VSS_PAD_P$90") (pintype "bidirectional"))
      (node (ref "U1") (pin "P$B7") (pinfunction "VSS_P$B7") (pintype "power_in"))
      (node (ref "U1") (pin "P$F23") (pinfunction "VSS_PA_P$F23") (pintype "bidirectional"))
      (node (ref "U3") (pin "1") (pinfunction "CTG_1") (pintype "power_in"))
      (node (ref "U3") (pin "4") (pinfunction "GND_4") (pintype "power_in"))
      (node (ref "U3") (pin "6") (pinfunction "QSTRT_6") (pintype "input"))
      (node (ref "U3") (pin "9") (pinfunction "EP_9") (pintype "power_in"))
      (node (ref "X1") (pin "2") (pinfunction "2_2") (pintype "passive"))
      (node (ref "X1") (pin "4") (pinfunction "4_4") (pintype "passive"))
    )
    (net (code "14") (name "HAPTIC_EN") (class "Default")
      (node (ref "IC2") (pin "A1") (pinfunction "EN_A1") (pintype "bidirectional"))
      (node (ref "U1") (pin "P$U1") (pinfunction "P0.12_P$U1") (pintype "bidirectional"))
    )
    (net (code "15") (name "IMU_INT1") (class "Default")
      (node (ref "IC3") (pin "5") (pinfunction "INT1_5") (pintype "bidirectional"))
      (node (ref "U1") (pin "P$N1") (pinfunction "P0.08_P$N1") (pintype "bidirectional"))
    )
    (net (code "16") (name "IMU_INT2") (class "Default")
      (node (ref "IC3") (pin "6") (pinfunction "INT2_6") (pintype "bidirectional"))
      (node (ref "U1") (pin "P$P2") (pinfunction "P1.08_P$P2") (pintype "bidirectional"))
    )
    (net (code "17") (name "LX1") (class "Default")
      (node (ref "IC9") (pin "B2") (pinfunction "SW1_1_B2") (pintype "bidirectional"))
      (node (ref "IC9") (pin "B3") (pinfunction "SW1_2_B3") (pintype "bidirectional"))
      (node (ref "L7") (pin "1") (pinfunction "1_1") (pintype "bidirectional"))
    )
    (net (code "18") (name "LX2") (class "Default")
      (node (ref "IC9") (pin "D2") (pinfunction "SW2_1_D2") (pintype "bidirectional"))
      (node (ref "IC9") (pin "D3") (pinfunction "SW2_2_D3") (pintype "bidirectional"))
      (node (ref "L7") (pin "2") (pinfunction "2_2") (pintype "bidirectional"))
    )
    (net (code "19") (name "MOSI") (class "Default")
      (node (ref "J1") (pin "14") (pinfunction "14_14") (pintype "bidirectional"))
      (node (ref "U1") (pin "P$B13") (pinfunction "P0.03/AIN1_P$B13") (pintype "bidirectional"))
    )
    (net (code "20") (name "Net-(ANT1-FEED)") (class "Default")
      (node (ref "ANT1") (pin "1") (pinfunction "FEED_1") (pintype "input"))
      (node (ref "C22") (pin "2") (pinfunction "2_2") (pintype "passive"))
      (node (ref "C4") (pin "2") (pinfunction "2_2") (pintype "passive"))
      (node (ref "L1") (pin "2") (pinfunction "2_2") (pintype "passive"))
    )
    (net (code "21") (name "Net-(D2-K)") (class "Default")
      (node (ref "C2-EP-DR") (pin "1") (pinfunction "1_1") (pintype "passive"))
      (node (ref "D2") (pin "1") (pinfunction "K_1") (pintype "bidirectional"))
      (node (ref "DE_PUS") (pin "2") (pinfunction "A_2") (pintype "bidirectional"))
    )
    (net (code "22") (name "Net-(D5-A)") (class "Default")
      (node (ref "C2-EP-DR") (pin "2") (pinfunction "2_2") (pintype "passive"))
      (node (ref "D5") (pin "2") (pinfunction "A_2") (pintype "bidirectional"))
      (node (ref "L5") (pin "1") (pinfunction "1_1") (pintype "passive"))
      (node (ref "Q3") (pin "3") (pinfunction "D_3") (pintype "bidirectional"))
    )
    (net (code "23") (name "Net-(EPD_C1-Pad2)") (class "Default")
      (node (ref "EPD_C1") (pin "2") (pinfunction "2_2") (pintype "passive"))
      (node (ref "J1") (pin "5") (pinfunction "5_5") (pintype "bidirectional"))
    )
    (net (code "24") (name "Net-(EPD_C2-Pad2)") (class "Default")
      (node (ref "EPD_C2") (pin "2") (pinfunction "2_2") (pintype "passive"))
      (node (ref "J1") (pin "4") (pinfunction "4_4") (pintype "bidirectional"))
    )
    (net (code "25") (name "Net-(EPD_C6-Pad2)") (class "Default")
      (node (ref "EPD_C6") (pin "2") (pinfunction "2_2") (pintype "passive"))
      (node (ref "J1") (pin "18") (pinfunction "18_18") (pintype "bidirectional"))
    )
    (net (code "26") (name "Net-(EPD_C7-Pad2)") (class "Default")
      (node (ref "EPD_C7") (pin "2") (pinfunction "2_2") (pintype "passive"))
      (node (ref "J1") (pin "19") (pinfunction "19_19") (pintype "bidirectional"))
    )
    (net (code "27") (name "Net-(EPD_C8-Pad2)") (class "Default")
      (node (ref "EPD_C8") (pin "2") (pinfunction "2_2") (pintype "passive"))
      (node (ref "J1") (pin "20") (pinfunction "20_20") (pintype "bidirectional"))
    )
    (net (code "28") (name "Net-(EPD_C10-Pad2)") (class "Default")
      (node (ref "EPD_C10") (pin "2") (pinfunction "2_2") (pintype "passive"))
      (node (ref "J1") (pin "22") (pinfunction "22_22") (pintype "bidirectional"))
    )
    (net (code "29") (name "Net-(EPD_C12-Pad2)") (class "Default")
      (node (ref "EPD_C12") (pin "2") (pinfunction "2_2") (pintype "passive"))
      (node (ref "J1") (pin "24") (pinfunction "24_24") (pintype "bidirectional"))
    )
    (net (code "30") (name "Net-(IC1-TS{slash}MR)") (class "Default")
      (node (ref "IC1") (pin "D1") (pinfunction "TS/MR_D1") (pintype "bidirectional"))
      (node (ref "R9") (pin "2") (pinfunction "2_2") (pintype "bidirectional"))
    )
    (net (code "31") (name "Net-(IC2-REG)") (class "Default")
      (node (ref "C32") (pin "2") (pinfunction "2_2") (pintype "passive"))
      (node (ref "IC2") (pin "A2") (pinfunction "REG_A2") (pintype "bidirectional"))
    )
    (net (code "32") (name "Net-(IC3-SDO)") (class "Default")
      (node (ref "IC3") (pin "1") (pinfunction "SDO_1") (pintype "bidirectional"))
      (node (ref "R3") (pin "2") (pinfunction "2_2") (pintype "bidirectional"))
    )
    (net (code "33") (name "Net-(IC9-SCL)") (class "Default")
      (node (ref "IC9") (pin "D1") (pinfunction "SCL_D1") (pintype "bidirectional"))
      (node (ref "R4") (pin "2") (pinfunction "2_2") (pintype "bidirectional"))
    )
    (net (code "34") (name "Net-(IC9-SDA)") (class "Default")
      (node (ref "IC9") (pin "E1") (pinfunction "SDA_E1") (pintype "bidirectional"))
      (node (ref "R2") (pin "2") (pinfunction "2_2") (pintype "bidirectional"))
    )
    (net (code "35") (name "Net-(J4-CC1)") (class "Default")
      (node (ref "J4") (pin "A5") (pinfunction "CC1_A5") (pintype "bidirectional"))
      (node (ref "R1_USB") (pin "2") (pinfunction "2_2") (pintype "bidirectional"))
    )
    (net (code "36") (name "Net-(J4-CC2)") (class "Default")
      (node (ref "J4") (pin "B5") (pinfunction "CC2_B5") (pintype "bidirectional"))
      (node (ref "R2_USB") (pin "1") (pinfunction "1_1") (pintype "bidirectional"))
    )
    (net (code "37") (name "Net-(L2-Pad1)") (class "Default")
      (node (ref "L2") (pin "1") (pinfunction "1_1") (pintype "passive"))
      (node (ref "L3") (pin "2") (pinfunction "2_2") (pintype "passive"))
    )
    (net (code "38") (name "Net-(R1_EP_DR-Pad1)") (class "Default")
      (node (ref "R1_EP_DR") (pin "1") (pinfunction "1_1") (pintype "bidirectional"))
      (node (ref "R_TYPE_SEL") (pin "2") (pinfunction "2_2") (pintype "bidirectional"))
      (node (ref "SJ1") (pin "2") (pinfunction "2_2") (pintype "passive"))
    )
    (net (code "39") (name "Net-(U1-ANT)") (class "Default")
      (node (ref "C3") (pin "2") (pinfunction "2_2") (pintype "passive"))
      (node (ref "L1") (pin "1") (pinfunction "1_1") (pintype "passive"))
      (node (ref "U1") (pin "P$H23") (pinfunction "ANT_P$H23") (pintype "bidirectional"))
    )
    (net (code "40") (name "Net-(U1-DCC)") (class "Default")
      (node (ref "L2") (pin "2") (pinfunction "2_2") (pintype "passive"))
      (node (ref "U1") (pin "P$B3") (pinfunction "DCC_P$B3") (pintype "output"))
    )
    (net (code "41") (name "Net-(U1-DEC1)") (class "Default")
      (node (ref "C5") (pin "2") (pinfunction "2_2") (pintype "passive"))
      (node (ref "U1") (pin "P$C1") (pinfunction "DEC1_P$C1") (pintype "power_in"))
    )
    (net (code "42") (name "Net-(U1-DEC2)") (class "Default")
      (node (ref "C13") (pin "1") (pinfunction "1_1") (pintype "passive"))
      (node (ref "U1") (pin "P$A18") (pinfunction "DEC2_P$A18") (pintype "bidirectional"))
    )
    (net (code "43") (name "Net-(U1-DEC3)") (class "Default")
      (node (ref "C11") (pin "1") (pinfunction "1_1") (pintype "passive"))
      (node (ref "U1") (pin "P$D23") (pinfunction "DEC3_P$D23") (pintype "bidirectional"))
    )
    (net (code "44") (name "Net-(U1-DEC3V3)") (class "Default")
      (node (ref "C20") (pin "2") (pinfunction "2_2") (pintype "passive"))
      (node (ref "U1") (pin "P$AC5") (pinfunction "DEC3V3_P$AC5") (pintype "bidirectional"))
    )
    (net (code "45") (name "Net-(U1-DEC4)") (class "Default")
      (node (ref "C10") (pin "1") (pinfunction "1_1") (pintype "passive"))
      (node (ref "C15") (pin "1") (pinfunction "1_1") (pintype "passive"))
      (node (ref "C16") (pin "1") (pinfunction "1_1") (pintype "passive"))
      (node (ref "L3") (pin "1") (pinfunction "1_1") (pintype "passive"))
      (node (ref "U1") (pin "P$B5") (pinfunction "DEC4_P$B5") (pintype "power_in"))
      (node (ref "U1") (pin "P$E24") (pinfunction "DEC6_P$E24") (pintype "bidirectional"))
    )
    (net (code "46") (name "Net-(U1-DEC5)") (class "Default")
      (node (ref "C9") (pin "1") (pinfunction "1_1") (pintype "passive"))
      (node (ref "U1") (pin "P$N24") (pinfunction "DEC5_P$N24") (pintype "bidirectional"))
    )
    (net (code "47") (name "Net-(U1-P0.00{slash}XL1)") (class "Default")
      (node (ref "C17") (pin "1") (pinfunction "1_1") (pintype "passive"))
      (node (ref "U1") (pin "P$D2") (pinfunction "P0.00/XL1_P$D2") (pintype "bidirectional"))
      (node (ref "X2") (pin "2") (pinfunction "2_2") (pintype "passive"))
    )
    (net (code "48") (name "Net-(U1-P0.01{slash}XL2)") (class "Default")
      (node (ref "C18") (pin "1") (pinfunction "1_1") (pintype "passive"))
      (node (ref "U1") (pin "P$F2") (pinfunction "P0.01/XL2_P$F2") (pintype "bidirectional"))
      (node (ref "X2") (pin "1") (pinfunction "1_1") (pintype "passive"))
    )
    (net (code "49") (name "Net-(U1-XC1)") (class "Default")
      (node (ref "C1") (pin "1") (pinfunction "1_1") (pintype "passive"))
      (node (ref "U1") (pin "P$B24") (pinfunction "XC1_P$B24") (pintype "input"))
      (node (ref "X1") (pin "1") (pinfunction "1_1") (pintype "passive"))
    )
    (net (code "50") (name "Net-(U1-XC2)") (class "Default")
      (node (ref "C2") (pin "1") (pinfunction "1_1") (pintype "passive"))
      (node (ref "U1") (pin "P$A23") (pinfunction "XC2_P$A23") (pintype "output"))
      (node (ref "X1") (pin "3") (pinfunction "3_3") (pintype "passive"))
    )
    (net (code "51") (name "OUT+") (class "Default")
      (node (ref "IC2") (pin "A3") (pinfunction "OUT+_A3") (pintype "bidirectional"))
      (node (ref "TP_OP") (pin "TP") (pinfunction "TP_TP") (pintype "input"))
    )
    (net (code "52") (name "OUT-") (class "Default")
      (node (ref "IC2") (pin "C3") (pinfunction "OUT-_C3") (pintype "bidirectional"))
      (node (ref "TP_ON") (pin "TP") (pinfunction "TP_TP") (pintype "input"))
    )
    (net (code "53") (name "P0.04") (class "Default")
      (node (ref "U1") (pin "P$J1") (pinfunction "P0.04/AIN2_P$J1") (pintype "bidirectional"))
    )
    (net (code "54") (name "P0.09") (class "Default")
      (node (ref "U1") (pin "P$L24") (pinfunction "P0.09/NFC1_P$L24") (pintype "bidirectional"))
    )
    (net (code "55") (name "P0.13") (class "Default")
      (node (ref "C30") (pin "2") (pinfunction "2_2") (pintype "passive"))
      (node (ref "R5") (pin "1") (pinfunction "1_1") (pintype "bidirectional"))
      (node (ref "SW_UP") (pin "2") (pinfunction "2_2") (pintype "passive"))
      (node (ref "U1") (pin "P$AD8") (pinfunction "P0.13_P$AD8") (pintype "bidirectional"))
    )
    (net (code "56") (name "P0.14") (class "Default")
      (node (ref "C31") (pin "2") (pinfunction "2_2") (pintype "passive"))
      (node (ref "R8") (pin "1") (pinfunction "1_1") (pintype "bidirectional"))
      (node (ref "SW_ENT") (pin "2") (pinfunction "2_2") (pintype "passive"))
      (node (ref "U1") (pin "P$AC9") (pinfunction "P0.14_P$AC9") (pintype "bidirectional"))
    )
    (net (code "57") (name "P0.19") (class "Default")
      (node (ref "U1") (pin "P$AC15") (pinfunction "P0.19_P$AC15") (pintype "bidirectional"))
    )
    (net (code "58") (name "P0.20") (class "Default")
      (node (ref "U1") (pin "P$AD16") (pinfunction "P0.20_P$AD16") (pintype "bidirectional"))
    )
    (net (code "59") (name "P0.21") (class "Default")
      (node (ref "U1") (pin "P$AC17") (pinfunction "P0.21_P$AC17") (pintype "bidirectional"))
    )
    (net (code "60") (name "P0.22") (class "Default")
      (node (ref "U1") (pin "P$AD18") (pinfunction "P0.22_P$AD18") (pintype "bidirectional"))
    )
    (net (code "61") (name "P0.23") (class "Default")
      (node (ref "U1") (pin "P$AC19") (pinfunction "P0.23_P$AC19") (pintype "bidirectional"))
    )
    (net (code "62") (name "P0.24") (class "Default")
      (node (ref "U1") (pin "P$AD20") (pinfunction "P0.24_P$AD20") (pintype "bidirectional"))
    )
    (net (code "63") (name "P0.25") (class "Default")
      (node (ref "U1") (pin "P$AC21") (pinfunction "P0.25_P$AC21") (pintype "bidirectional"))
    )
    (net (code "64") (name "P0.26") (class "Default")
      (node (ref "U1") (pin "P$G1") (pinfunction "P0.26_P$G1") (pintype "bidirectional"))
    )
    (net (code "65") (name "P0.27") (class "Default")
      (node (ref "U1") (pin "P$H2") (pinfunction "P0.27_P$H2") (pintype "bidirectional"))
    )
    (net (code "66") (name "P0.28") (class "Default")
      (node (ref "U1") (pin "P$B11") (pinfunction "P0.28/AIN4_P$B11") (pintype "bidirectional"))
    )
    (net (code "67") (name "P0.29") (class "Default")
      (node (ref "U1") (pin "P$A10") (pinfunction "P0.29/AIN5_P$A10") (pintype "bidirectional"))
    )
    (net (code "68") (name "P0.30") (class "Default")
      (node (ref "U1") (pin "P$B9") (pinfunction "P0.30/AIN6_P$B9") (pintype "bidirectional"))
    )
    (net (code "69") (name "P0.31") (class "Default")
      (node (ref "U1") (pin "P$A8") (pinfunction "P0.31/AIN7_P$A8") (pintype "bidirectional"))
    )
    (net (code "70") (name "P1.01") (class "Default")
      (node (ref "Q1") (pin "1") (pinfunction "G_1") (pintype "bidirectional"))
      (node (ref "R_PWR_EPD") (pin "1") (pinfunction "1_1") (pintype "bidirectional"))
      (node (ref "U1") (pin "P$Y23") (pinfunction "P1.01_P$Y23") (pintype "bidirectional"))
    )
    (net (code "71") (name "P1.02") (class "Default")
      (node (ref "C29") (pin "2") (pinfunction "2_2") (pintype "passive"))
      (node (ref "R7") (pin "1") (pinfunction "1_1") (pintype "bidirectional"))
      (node (ref "SW_DN") (pin "2") (pinfunction "2_2") (pintype "passive"))
      (node (ref "U1") (pin "P$W24") (pinfunction "P1.02_P$W24") (pintype "bidirectional"))
    )
    (net (code "72") (name "P1.03") (class "Default")
      (node (ref "U1") (pin "P$V23") (pinfunction "P1.03_P$V23") (pintype "bidirectional"))
    )
    (net (code "73") (name "P1.04") (class "Default")
      (node (ref "U1") (pin "P$U24") (pinfunction "P1.04_P$U24") (pintype "bidirectional"))
    )
    (net (code "74") (name "P1.05") (class "Default")
      (node (ref "U1") (pin "P$T23") (pinfunction "P1.05_P$T23") (pintype "bidirectional"))
    )
    (net (code "75") (name "P1.06") (class "Default")
      (node (ref "U1") (pin "P$R24") (pinfunction "P1.06_P$R24") (pintype "bidirectional"))
    )
    (net (code "76") (name "P1.07") (class "Default")
      (node (ref "U1") (pin "P$P23") (pinfunction "P1.07_P$P23") (pintype "bidirectional"))
    )
    (net (code "77") (name "P1.09") (class "Default")
      (node (ref "U1") (pin "P$R1") (pinfunction "P1.09_P$R1") (pintype "bidirectional"))
    )
    (net (code "78") (name "P1.10") (class "Default")
      (node (ref "U1") (pin "P$A20") (pinfunction "P1.10_P$A20") (pintype "bidirectional"))
    )
    (net (code "79") (name "P1.11") (class "Default")
      (node (ref "U1") (pin "P$B19") (pinfunction "P1.11_P$B19") (pintype "bidirectional"))
    )
    (net (code "80") (name "P1.12") (class "Default")
      (node (ref "U1") (pin "P$B17") (pinfunction "P1.12_P$B17") (pintype "bidirectional"))
    )
    (net (code "81") (name "P1.13") (class "Default")
      (node (ref "U1") (pin "P$A16") (pinfunction "P1.13_P$A16") (pintype "bidirectional"))
    )
    (net (code "82") (name "P1.14") (class "Default")
      (node (ref "U1") (pin "P$B15") (pinfunction "P1.14_P$B15") (pintype "bidirectional"))
    )
    (net (code "83") (name "P1.15") (class "Default")
      (node (ref "U1") (pin "P$A14") (pinfunction "P1.15_P$A14") (pintype "bidirectional"))
    )
    (net (code "84") (name "PMIC_INT") (class "Default")
      (node (ref "IC1") (pin "A1") (pinfunction "~{INT}_A1") (pintype "bidirectional"))
      (node (ref "U1") (pin "P$T2") (pinfunction "P0.11_P$T2") (pintype "bidirectional"))
    )
    (net (code "85") (name "PREVGH") (class "Default")
      (node (ref "D5") (pin "1") (pinfunction "K_1") (pintype "bidirectional"))
      (node (ref "EPD_C9") (pin "2") (pinfunction "2_2") (pintype "passive"))
      (node (ref "J1") (pin "21") (pinfunction "21_21") (pintype "bidirectional"))
    )
    (net (code "86") (name "PREVGL") (class "Default")
      (node (ref "D2") (pin "2") (pinfunction "A_2") (pintype "bidirectional"))
      (node (ref "EPD_C11") (pin "2") (pinfunction "2_2") (pintype "passive"))
      (node (ref "J1") (pin "23") (pinfunction "23_23") (pintype "bidirectional"))
    )
    (net (code "87") (name "RESE") (class "Default")
      (node (ref "J1") (pin "3") (pinfunction "3_3") (pintype "bidirectional"))
      (node (ref "Q3") (pin "2") (pinfunction "S_2") (pintype "bidirectional"))
      (node (ref "R1_EP_DR") (pin "2") (pinfunction "2_2") (pintype "bidirectional"))
    )
    (net (code "88") (name "RESET") (class "Default")
      (node (ref "J2") (pin "6") (pinfunction "6_6") (pintype "bidirectional"))
      (node (ref "TP_RESET") (pin "TP") (pinfunction "TP_TP") (pintype "input"))
      (node (ref "U1") (pin "P$AC13") (pinfunction "P0.18/RESET_P$AC13") (pintype "bidirectional"))
    )
    (net (code "89") (name "SCK") (class "Default")
      (node (ref "J1") (pin "13") (pinfunction "13_13") (pintype "bidirectional"))
      (node (ref "U1") (pin "P$A12") (pinfunction "P0.02/AIN0_P$A12") (pintype "bidirectional"))
    )
    (net (code "90") (name "SCL") (class "Default")
      (node (ref "IC1") (pin "B1") (pinfunction "SCL_B1") (pintype "bidirectional"))
      (node (ref "IC2") (pin "C1") (pinfunction "SCL_C1") (pintype "bidirectional"))
      (node (ref "IC3") (pin "12") (pinfunction "SCX_12") (pintype "bidirectional"))
      (node (ref "R17") (pin "2") (pinfunction "2_2") (pintype "bidirectional"))
      (node (ref "R4") (pin "1") (pinfunction "1_1") (pintype "bidirectional"))
      (node (ref "TP_SCL") (pin "TP") (pinfunction "TP_TP") (pintype "input"))
      (node (ref "U1") (pin "P$M2") (pinfunction "P0.07_P$M2") (pintype "bidirectional"))
      (node (ref "U3") (pin "7") (pinfunction "SCL_7") (pintype "input"))
    )
    (net (code "91") (name "SDA") (class "Default")
      (node (ref "IC1") (pin "C1") (pinfunction "SDA_C1") (pintype "bidirectional"))
      (node (ref "IC2") (pin "B2") (pinfunction "SDA_B2") (pintype "bidirectional"))
      (node (ref "IC3") (pin "2") (pinfunction "SDX_2") (pintype "bidirectional"))
      (node (ref "R18") (pin "2") (pinfunction "2_2") (pintype "bidirectional"))
      (node (ref "R2") (pin "1") (pinfunction "1_1") (pintype "bidirectional"))
      (node (ref "TP_SDA") (pin "TP") (pinfunction "TP_TP") (pintype "input"))
      (node (ref "U1") (pin "P$L1") (pinfunction "P0.06_P$L1") (pintype "bidirectional"))
      (node (ref "U3") (pin "8") (pinfunction "SDA_8") (pintype "bidirectional"))
    )
    (net (code "92") (name "SWDCLK") (class "Default")
      (node (ref "J2") (pin "4") (pinfunction "4_4") (pintype "bidirectional"))
      (node (ref "TP_SWDCLK") (pin "TP") (pinfunction "TP_TP") (pintype "input"))
      (node (ref "U1") (pin "P$AA24") (pinfunction "SWDCLK_P$AA24") (pintype "input"))
    )
    (net (code "93") (name "SWDIO") (class "Default")
      (node (ref "J2") (pin "2") (pinfunction "2_2") (pintype "bidirectional"))
      (node (ref "TP_SWDIO") (pin "TP") (pinfunction "TP_TP") (pintype "input"))
      (node (ref "U1") (pin "P$AC24") (pinfunction "SWDIO_P$AC24") (pintype "bidirectional"))
    )
    (net (code "94") (name "SWO") (class "Default")
      (node (ref "TP_SWO") (pin "TP") (pinfunction "TP_TP") (pintype "input"))
      (node (ref "U1") (pin "P$AD22") (pinfunction "P1.00_P$AD22") (pintype "bidirectional"))
    )
    (net (code "95") (name "VBAT") (class "Default")
      (node (ref "C27") (pin "2") (pinfunction "2_2") (pintype "passive"))
      (node (ref "C37") (pin "2") (pinfunction "2_2") (pintype "passive"))
      (node (ref "IC1") (pin "C2") (pinfunction "BAT_C2") (pintype "bidirectional"))
      (node (ref "TP_VBAT") (pin "TP") (pinfunction "TP_TP") (pintype "input"))
      (node (ref "U3") (pin "2") (pinfunction "CELL_2") (pintype "power_in"))
      (node (ref "U3") (pin "3") (pinfunction "VDD_3") (pintype "power_in"))
    )
    (net (code "96") (name "VBUS") (class "Default")
      (node (ref "C21") (pin "1") (pinfunction "1_1") (pintype "passive"))
      (node (ref "C38") (pin "2") (pinfunction "2_2") (pintype "passive"))
      (node (ref "C42") (pin "1") (pinfunction "1_1") (pintype "passive"))
      (node (ref "C43") (pin "1") (pinfunction "1_1") (pintype "passive"))
      (node (ref "D3") (pin "5") (pinfunction "VBUS_5") (pintype "bidirectional"))
      (node (ref "IC1") (pin "A2") (pinfunction "IN_A2") (pintype "bidirectional"))
      (node (ref "J4") (pin "A4_B9") (pinfunction "VBUS_A4_B9") (pintype "power_in"))
      (node (ref "J4") (pin "A9_B4") (pinfunction "VBUS_A9_B4") (pintype "power_in"))
      (node (ref "U1") (pin "P$AD2") (pinfunction "VBUS_P$AD2") (pintype "power_in"))
    )
    (net (code "97") (name "VREG") (class "Default")
      (node (ref "C23") (pin "2") (pinfunction "2_2") (pintype "passive"))
      (node (ref "C24") (pin "2") (pinfunction "2_2") (pintype "passive"))
      (node (ref "C39") (pin "1") (pinfunction "1_1") (pintype "passive"))
      (node (ref "IC1") (pin "B2") (pinfunction "SYS_B2") (pintype "bidirectional"))
      (node (ref "IC9") (pin "A1") (pinfunction "EN_A1") (pintype "bidirectional"))
      (node (ref "IC9") (pin "A2") (pinfunction "VIN_1_A2") (pintype "bidirectional"))
      (node (ref "IC9") (pin "A3") (pinfunction "VIN_2_A3") (pintype "bidirectional"))
      (node (ref "TP_VREG") (pin "TP") (pinfunction "TP_TP") (pintype "input"))
    )
    (net (code "98") (name "unconnected-(ANT1-NC-Pad2)") (class "Default")
      (node (ref "ANT1") (pin "2") (pinfunction "NC_2") (pintype "no_connect"))
    )
    (net (code "99") (name "unconnected-(IC3-ASCL-Pad11)") (class "Default")
      (node (ref "IC3") (pin "11") (pinfunction "ASCL_11") (pintype "bidirectional"))
    )
    (net (code "100") (name "unconnected-(IC3-ASDA-Pad4)") (class "Default")
      (node (ref "IC3") (pin "4") (pinfunction "ASDA_4") (pintype "bidirectional"))
    )
    (net (code "101") (name "unconnected-(J1-Pad1)") (class "Default")
      (node (ref "J1") (pin "1") (pinfunction "1_1") (pintype "bidirectional"))
    )
    (net (code "102") (name "unconnected-(J1-Pad6)") (class "Default")
      (node (ref "J1") (pin "6") (pinfunction "6_6") (pintype "bidirectional"))
    )
    (net (code "103") (name "unconnected-(J1-Pad7)") (class "Default")
      (node (ref "J1") (pin "7") (pinfunction "7_7") (pintype "bidirectional"))
    )
    (net (code "104") (name "unconnected-(J4-SBU1-PadA8)") (class "Default")
      (node (ref "J4") (pin "A8") (pinfunction "SBU1_A8") (pintype "bidirectional"))
    )
    (net (code "105") (name "unconnected-(J4-SBU2-PadB8)") (class "Default")
      (node (ref "J4") (pin "B8") (pinfunction "SBU2_B8") (pintype "bidirectional"))
    )
    (net (code "106") (name "unconnected-(U1-DCCH-PadP$AB2)") (class "Default")
      (node (ref "U1") (pin "P$AB2") (pinfunction "DCCH_P$AB2") (pintype "bidirectional"))
    )
  )
)
